# main.net
KiCad netlist of a schematic drawn in EAGLE
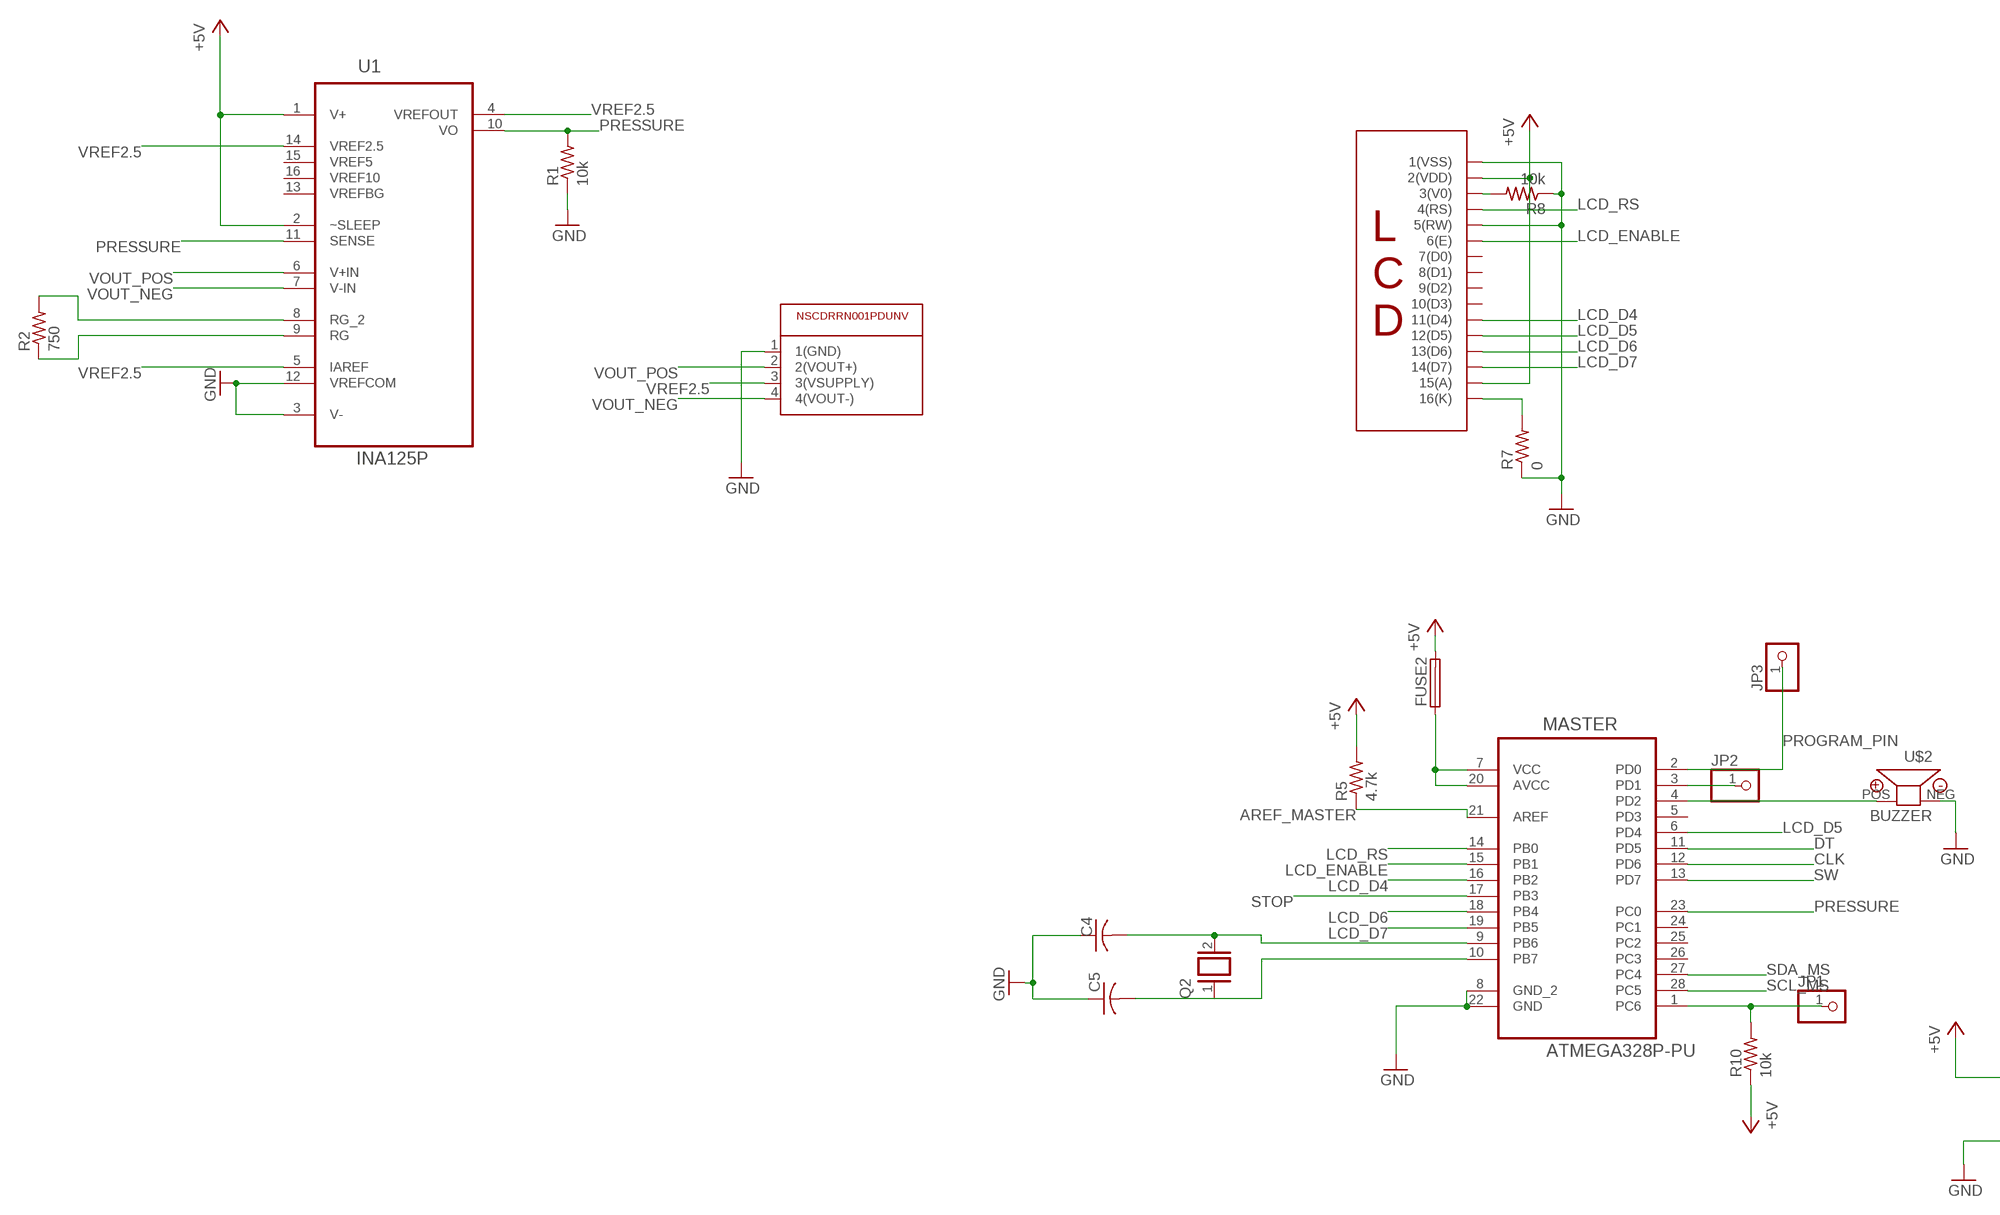
[diagram p0: schematic, sheet 1, part 1 of 2]
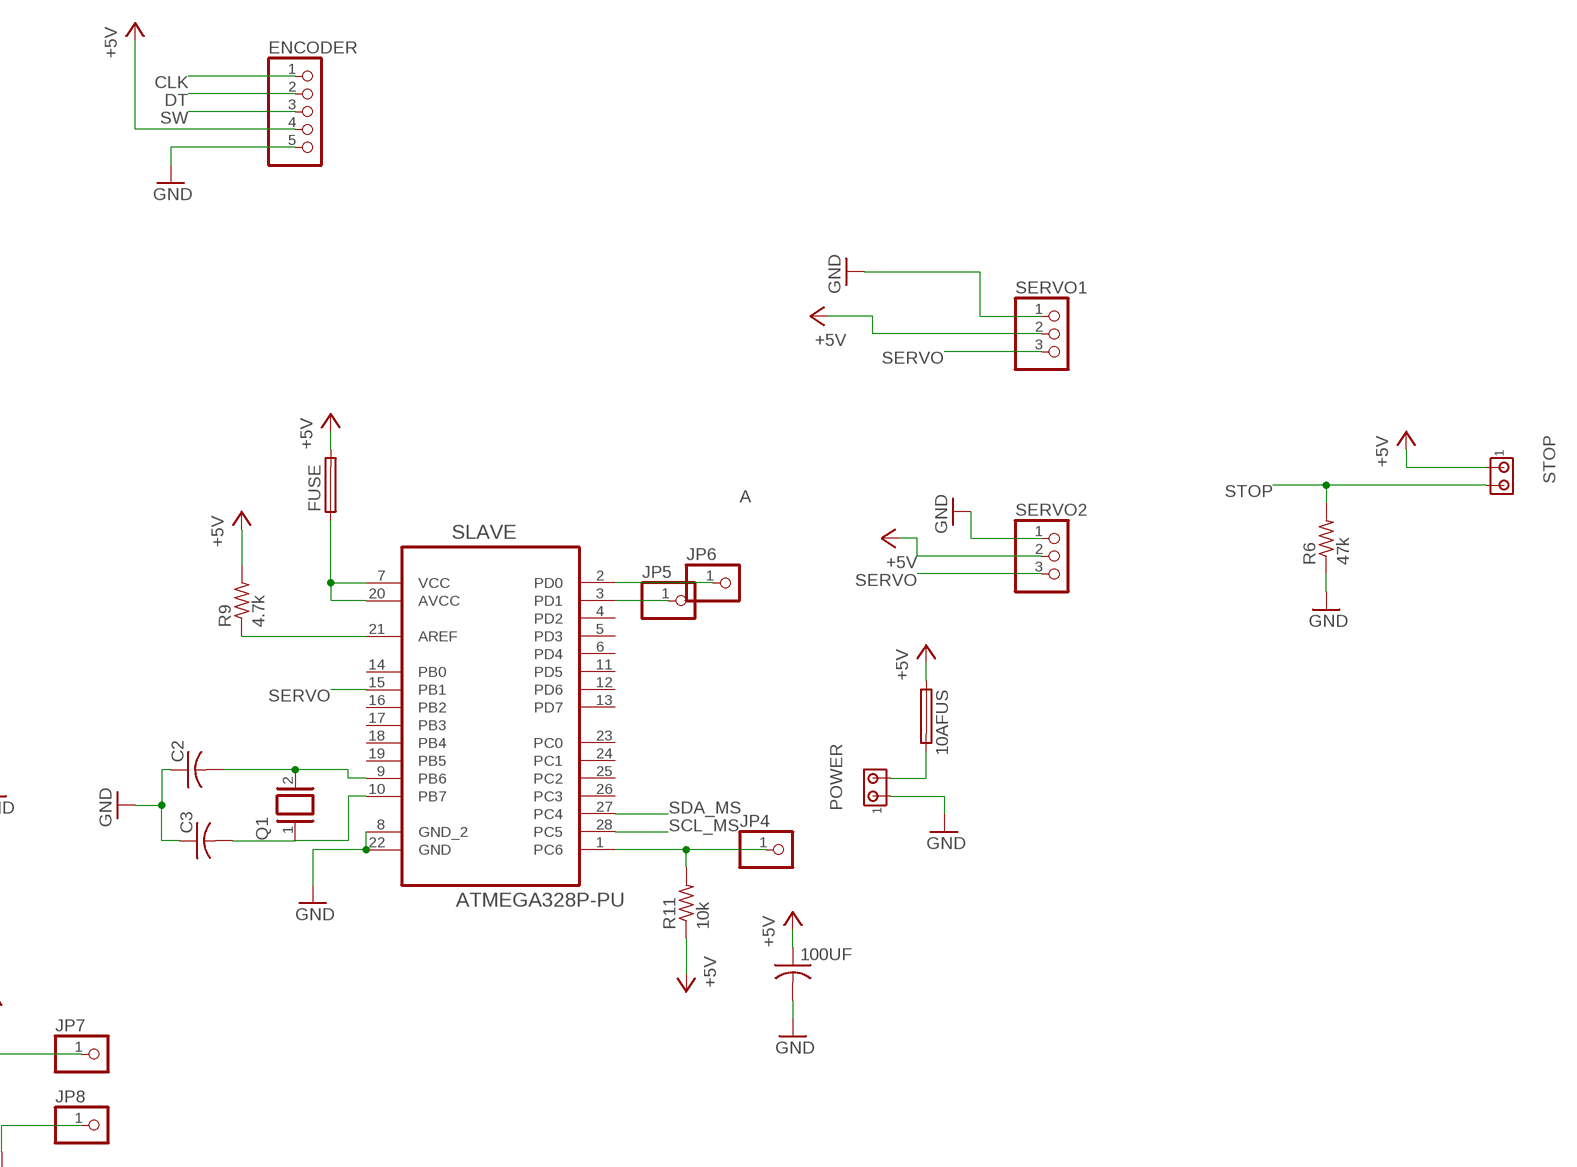
[diagram p1: schematic, sheet 1, part 2 of 2]

(export (version "E")
  (design (tool "Eeschema 10.0.6"))
  (components
    (comp (ref "10AFUS")
      (value "FUSE050-075X075")
      (footprint "eagle-import:C050-075X075")
      (libsource (lib "eagle-import") (part "FUSE050-075X075"))
    )
    (comp (ref "100UF")
      (value "5MM_CAPACITOR050-075X075")
      (footprint "eagle-import:C050-075X075")
      (libsource (lib "eagle-import") (part "5MM_CAPACITOR050-075X075"))
    )
    (comp (ref "C2")
      (value "5MM_CAPACITOR050-075X075")
      (footprint "eagle-import:C050-075X075")
      (libsource (lib "eagle-import") (part "5MM_CAPACITOR050-075X075"))
    )
    (comp (ref "C3")
      (value "5MM_CAPACITOR050-075X075")
      (footprint "eagle-import:C050-075X075")
      (libsource (lib "eagle-import") (part "5MM_CAPACITOR050-075X075"))
    )
    (comp (ref "C4")
      (value "5MM_CAPACITOR050-075X075")
      (footprint "eagle-import:C050-075X075")
      (libsource (lib "eagle-import") (part "5MM_CAPACITOR050-075X075"))
    )
    (comp (ref "C5")
      (value "5MM_CAPACITOR050-075X075")
      (footprint "eagle-import:C050-075X075")
      (libsource (lib "eagle-import") (part "5MM_CAPACITOR050-075X075"))
    )
    (comp (ref "ENCODER")
      (value "PINHD-1X5")
      (footprint "eagle-import:1X05")
      (libsource (lib "eagle-import") (part "PINHD-1X5"))
    )
    (comp (ref "FUSE")
      (value "FUSE050-075X075")
      (footprint "eagle-import:C050-075X075")
      (libsource (lib "eagle-import") (part "FUSE050-075X075"))
    )
    (comp (ref "FUSE2")
      (value "FUSE050-075X075")
      (footprint "eagle-import:C050-075X075")
      (libsource (lib "eagle-import") (part "FUSE050-075X075"))
    )
    (comp (ref "JP1")
      (value "PINHD-1X1")
      (footprint "eagle-import:1X01")
      (libsource (lib "eagle-import") (part "PINHD-1X1"))
    )
    (comp (ref "JP2")
      (value "PINHD-1X1")
      (footprint "eagle-import:1X01")
      (libsource (lib "eagle-import") (part "PINHD-1X1"))
    )
    (comp (ref "JP3")
      (value "PINHD-1X1")
      (footprint "eagle-import:1X01")
      (libsource (lib "eagle-import") (part "PINHD-1X1"))
    )
    (comp (ref "JP4")
      (value "PINHD-1X1")
      (footprint "eagle-import:1X01")
      (libsource (lib "eagle-import") (part "PINHD-1X1"))
    )
    (comp (ref "JP5")
      (value "PINHD-1X1")
      (footprint "eagle-import:1X01")
      (libsource (lib "eagle-import") (part "PINHD-1X1"))
    )
    (comp (ref "JP6")
      (value "PINHD-1X1")
      (footprint "eagle-import:1X01")
      (libsource (lib "eagle-import") (part "PINHD-1X1"))
    )
    (comp (ref "JP7")
      (value "PINHD-1X1")
      (footprint "eagle-import:1X01")
      (libsource (lib "eagle-import") (part "PINHD-1X1"))
    )
    (comp (ref "JP8")
      (value "PINHD-1X1")
      (footprint "eagle-import:1X01")
      (libsource (lib "eagle-import") (part "PINHD-1X1"))
    )
    (comp (ref "MASTER")
      (value "ATMEGA328P-PU")
      (footprint "eagle-import:DIP254P762X457-28")
      (fields (field (name "MF") "Microchip"))
      (libsource (lib "eagle-import") (part "ATMEGA328P-PU"))
    )
    (comp (ref "POWER")
      (value "MTA02-156")
      (footprint "eagle-import:1X2MTA")
      (libsource (lib "eagle-import") (part "MTA02-156"))
    )
    (comp (ref "Q1")
      (value "XTAL/S")
      (footprint "eagle-import:QS")
      (libsource (lib "eagle-import") (part "XTAL/S"))
    )
    (comp (ref "Q2")
      (value "XTAL/S")
      (footprint "eagle-import:QS")
      (libsource (lib "eagle-import") (part "XTAL/S"))
    )
    (comp (ref "R1")
      (value "10k")
      (footprint "eagle-import:0207_10")
      (libsource (lib "eagle-import") (part "R-US_0207/10"))
    )
    (comp (ref "R2")
      (value "750")
      (footprint "eagle-import:0207_10")
      (libsource (lib "eagle-import") (part "R-US_0207/10"))
    )
    (comp (ref "R5")
      (value "4.7k")
      (footprint "eagle-import:0207_10")
      (libsource (lib "eagle-import") (part "R-US_0207/10"))
    )
    (comp (ref "R6")
      (value "47k")
      (footprint "eagle-import:0207_10")
      (libsource (lib "eagle-import") (part "R-US_0207/10"))
    )
    (comp (ref "R7")
      (value "0")
      (footprint "eagle-import:0207_10")
      (libsource (lib "eagle-import") (part "R-US_0207/10"))
    )
    (comp (ref "R8")
      (value "10k")
      (footprint "eagle-import:0207_10")
      (libsource (lib "eagle-import") (part "R-US_0207/10"))
    )
    (comp (ref "R9")
      (value "4.7k")
      (footprint "eagle-import:0207_10")
      (libsource (lib "eagle-import") (part "R-US_0207/10"))
    )
    (comp (ref "R10")
      (value "10k")
      (footprint "eagle-import:0207_10")
      (libsource (lib "eagle-import") (part "R-US_0207/10"))
    )
    (comp (ref "R11")
      (value "10k")
      (footprint "eagle-import:0207_10")
      (libsource (lib "eagle-import") (part "R-US_0207/10"))
    )
    (comp (ref "SERVO1")
      (value "PINHD-1X3/90")
      (footprint "eagle-import:1X03_90")
      (libsource (lib "eagle-import") (part "PINHD-1X3/90"))
    )
    (comp (ref "SERVO2")
      (value "PINHD-1X3/90")
      (footprint "eagle-import:1X03_90")
      (libsource (lib "eagle-import") (part "PINHD-1X3/90"))
    )
    (comp (ref "SLAVE")
      (value "ATMEGA328P-PU")
      (footprint "eagle-import:DIP254P762X457-28")
      (fields (field (name "MF") "Microchip"))
      (libsource (lib "eagle-import") (part "ATMEGA328P-PU"))
    )
    (comp (ref "STOP")
      (value "MTA02-156")
      (footprint "eagle-import:1X2MTA")
      (libsource (lib "eagle-import") (part "MTA02-156"))
    )
    (comp (ref "U$1")
      (value "LCD")
      (footprint "eagle-import:1X16")
      (libsource (lib "eagle-import") (part "LCD"))
    )
    (comp (ref "U$2")
      (value "BUZZER")
      (footprint "eagle-import:BUZZER")
      (libsource (lib "eagle-import") (part "BUZZER"))
    )
    (comp (ref "U$3")
      (value "PRESSURE_SENSOR")
      (footprint "eagle-import:DIP8-WIDE")
      (libsource (lib "eagle-import") (part "PRESSURE_SENSOR"))
    )
    (comp (ref "U1")
      (value "INA125P")
      (footprint "eagle-import:DIP254P762X508-16")
      (fields (field (name "MF") "Texas Instruments"))
      (libsource (lib "eagle-import") (part "INA125P"))
    )
  )
  (nets
    (net (code "1") (name "+5V") (class "Default")
      (node (ref "100UF") (pin "1") (pinfunction "1_1") (pintype "passive"))
      (node (ref "10AFUS") (pin "1") (pinfunction "1_1") (pintype "passive"))
      (node (ref "ENCODER") (pin "4") (pinfunction "4_4") (pintype "passive"))
      (node (ref "FUSE") (pin "2") (pinfunction "2_2") (pintype "passive"))
      (node (ref "FUSE2") (pin "2") (pinfunction "2_2") (pintype "passive"))
      (node (ref "JP7") (pin "1") (pinfunction "1_1") (pintype "passive"))
      (node (ref "R10") (pin "1") (pinfunction "1_1") (pintype "passive"))
      (node (ref "R11") (pin "1") (pinfunction "1_1") (pintype "passive"))
      (node (ref "R5") (pin "2") (pinfunction "2_2") (pintype "passive"))
      (node (ref "R9") (pin "2") (pinfunction "2_2") (pintype "passive"))
      (node (ref "SERVO1") (pin "2") (pinfunction "2_2") (pintype "passive"))
      (node (ref "SERVO2") (pin "2") (pinfunction "2_2") (pintype "passive"))
      (node (ref "STOP") (pin "1") (pinfunction "1_1") (pintype "passive"))
      (node (ref "U$1") (pin "15") (pinfunction "15(A)_15") (pintype "bidirectional"))
      (node (ref "U$1") (pin "2") (pinfunction "2(VDD)_2") (pintype "bidirectional"))
      (node (ref "U1") (pin "1") (pinfunction "V+_1") (pintype "power_in"))
      (node (ref "U1") (pin "2") (pinfunction "~{SLEEP}_2") (pintype "passive"))
    )
    (net (code "2") (name "/A") (class "Default")
      (node (ref "JP6") (pin "1") (pinfunction "1_1") (pintype "passive"))
      (node (ref "SLAVE") (pin "2") (pinfunction "PD0_2") (pintype "bidirectional"))
    )
    (net (code "3") (name "/AREF_MASTER") (class "Default")
      (node (ref "MASTER") (pin "21") (pinfunction "AREF_21") (pintype "input"))
      (node (ref "R5") (pin "1") (pinfunction "1_1") (pintype "passive"))
    )
    (net (code "4") (name "/CLK") (class "Default")
      (node (ref "ENCODER") (pin "1") (pinfunction "1_1") (pintype "passive"))
      (node (ref "MASTER") (pin "12") (pinfunction "PD6_12") (pintype "bidirectional"))
    )
    (net (code "5") (name "/DT") (class "Default")
      (node (ref "ENCODER") (pin "2") (pinfunction "2_2") (pintype "passive"))
      (node (ref "MASTER") (pin "11") (pinfunction "PD5_11") (pintype "bidirectional"))
    )
    (net (code "6") (name "/LCD_D4") (class "Default")
      (node (ref "MASTER") (pin "16") (pinfunction "PB2_16") (pintype "bidirectional"))
      (node (ref "U$1") (pin "11") (pinfunction "11(D4)_11") (pintype "bidirectional"))
    )
    (net (code "7") (name "/LCD_D5") (class "Default")
      (node (ref "MASTER") (pin "6") (pinfunction "PD4_6") (pintype "bidirectional"))
      (node (ref "U$1") (pin "12") (pinfunction "12(D5)_12") (pintype "bidirectional"))
    )
    (net (code "8") (name "/LCD_D6") (class "Default")
      (node (ref "MASTER") (pin "18") (pinfunction "PB4_18") (pintype "bidirectional"))
      (node (ref "U$1") (pin "13") (pinfunction "13(D6)_13") (pintype "bidirectional"))
    )
    (net (code "9") (name "/LCD_D7") (class "Default")
      (node (ref "MASTER") (pin "19") (pinfunction "PB5_19") (pintype "bidirectional"))
      (node (ref "U$1") (pin "14") (pinfunction "14(D7)_14") (pintype "bidirectional"))
    )
    (net (code "10") (name "/LCD_ENABLE") (class "Default")
      (node (ref "MASTER") (pin "15") (pinfunction "PB1_15") (pintype "bidirectional"))
      (node (ref "U$1") (pin "6") (pinfunction "6(E)_6") (pintype "bidirectional"))
    )
    (net (code "11") (name "/LCD_RS") (class "Default")
      (node (ref "MASTER") (pin "14") (pinfunction "PB0_14") (pintype "bidirectional"))
      (node (ref "U$1") (pin "4") (pinfunction "4(RS)_4") (pintype "bidirectional"))
    )
    (net (code "12") (name "/PRESSURE") (class "Default")
      (node (ref "MASTER") (pin "23") (pinfunction "PC0_23") (pintype "bidirectional"))
      (node (ref "R1") (pin "2") (pinfunction "2_2") (pintype "passive"))
      (node (ref "U1") (pin "10") (pinfunction "VO_10") (pintype "output"))
      (node (ref "U1") (pin "11") (pinfunction "SENSE_11") (pintype "input"))
    )
    (net (code "13") (name "/PROGRAM_PIN") (class "Default")
      (node (ref "JP3") (pin "1") (pinfunction "1_1") (pintype "passive"))
      (node (ref "MASTER") (pin "2") (pinfunction "PD0_2") (pintype "bidirectional"))
    )
    (net (code "14") (name "/SCL_MS") (class "Default")
      (node (ref "MASTER") (pin "28") (pinfunction "PC5_28") (pintype "bidirectional"))
      (node (ref "SLAVE") (pin "28") (pinfunction "PC5_28") (pintype "bidirectional"))
    )
    (net (code "15") (name "/SDA_MS") (class "Default")
      (node (ref "MASTER") (pin "27") (pinfunction "PC4_27") (pintype "bidirectional"))
      (node (ref "SLAVE") (pin "27") (pinfunction "PC4_27") (pintype "bidirectional"))
    )
    (net (code "16") (name "/SERVO") (class "Default")
      (node (ref "SERVO1") (pin "3") (pinfunction "3_3") (pintype "passive"))
      (node (ref "SERVO2") (pin "3") (pinfunction "3_3") (pintype "passive"))
      (node (ref "SLAVE") (pin "15") (pinfunction "PB1_15") (pintype "bidirectional"))
    )
    (net (code "17") (name "/STOP") (class "Default")
      (node (ref "MASTER") (pin "17") (pinfunction "PB3_17") (pintype "bidirectional"))
      (node (ref "R6") (pin "2") (pinfunction "2_2") (pintype "passive"))
      (node (ref "STOP") (pin "2") (pinfunction "2_2") (pintype "passive"))
    )
    (net (code "18") (name "/SW") (class "Default")
      (node (ref "ENCODER") (pin "3") (pinfunction "3_3") (pintype "passive"))
      (node (ref "MASTER") (pin "13") (pinfunction "PD7_13") (pintype "bidirectional"))
    )
    (net (code "19") (name "/VOUT_NEG") (class "Default")
      (node (ref "U$3") (pin "4") (pinfunction "4(VOUT-)_4") (pintype "bidirectional"))
      (node (ref "U1") (pin "7") (pinfunction "V-IN_7") (pintype "power_in"))
    )
    (net (code "20") (name "/VOUT_POS") (class "Default")
      (node (ref "U$3") (pin "2") (pinfunction "2(VOUT+)_2") (pintype "bidirectional"))
      (node (ref "U1") (pin "6") (pinfunction "V+IN_6") (pintype "power_in"))
    )
    (net (code "21") (name "/VREF2.5") (class "Default")
      (node (ref "U$3") (pin "3") (pinfunction "3(VSUPPLY)_3") (pintype "bidirectional"))
      (node (ref "U1") (pin "14") (pinfunction "VREF2.5_14") (pintype "power_in"))
      (node (ref "U1") (pin "4") (pinfunction "VREFOUT_4") (pintype "output"))
      (node (ref "U1") (pin "5") (pinfunction "IAREF_5") (pintype "passive"))
    )
    (net (code "22") (name "/VREF5") (class "Default")
      (node (ref "U1") (pin "15") (pinfunction "VREF5_15") (pintype "power_in"))
    )
    (net (code "23") (name "/VREF10") (class "Default")
      (node (ref "U1") (pin "16") (pinfunction "VREF10_16") (pintype "power_in"))
    )
    (net (code "24") (name "/VREFBG") (class "Default")
      (node (ref "U1") (pin "13") (pinfunction "VREFBG_13") (pintype "power_in"))
    )
    (net (code "25") (name "GND") (class "Default")
      (node (ref "100UF") (pin "2") (pinfunction "2_2") (pintype "passive"))
      (node (ref "C2") (pin "1") (pinfunction "1_1") (pintype "passive"))
      (node (ref "C3") (pin "1") (pinfunction "1_1") (pintype "passive"))
      (node (ref "C4") (pin "1") (pinfunction "1_1") (pintype "passive"))
      (node (ref "C5") (pin "1") (pinfunction "1_1") (pintype "passive"))
      (node (ref "ENCODER") (pin "5") (pinfunction "5_5") (pintype "passive"))
      (node (ref "JP8") (pin "1") (pinfunction "1_1") (pintype "passive"))
      (node (ref "MASTER") (pin "22") (pinfunction "GND_22") (pintype "passive"))
      (node (ref "MASTER") (pin "8") (pinfunction "GND_2_8") (pintype "passive"))
      (node (ref "POWER") (pin "1") (pinfunction "1_1") (pintype "passive"))
      (node (ref "R1") (pin "1") (pinfunction "1_1") (pintype "passive"))
      (node (ref "R6") (pin "1") (pinfunction "1_1") (pintype "passive"))
      (node (ref "R7") (pin "1") (pinfunction "1_1") (pintype "passive"))
      (node (ref "R8") (pin "1") (pinfunction "1_1") (pintype "passive"))
      (node (ref "SERVO1") (pin "1") (pinfunction "1_1") (pintype "passive"))
      (node (ref "SERVO2") (pin "1") (pinfunction "1_1") (pintype "passive"))
      (node (ref "SLAVE") (pin "22") (pinfunction "GND_22") (pintype "passive"))
      (node (ref "SLAVE") (pin "8") (pinfunction "GND_2_8") (pintype "passive"))
      (node (ref "U$1") (pin "1") (pinfunction "1(VSS)_1") (pintype "bidirectional"))
      (node (ref "U$1") (pin "5") (pinfunction "5(RW)_5") (pintype "bidirectional"))
      (node (ref "U$2") (pin "NEG") (pinfunction "NEG_NEG") (pintype "passive"))
      (node (ref "U$3") (pin "1") (pinfunction "1(GND)_1") (pintype "bidirectional"))
      (node (ref "U1") (pin "12") (pinfunction "VREFCOM_12") (pintype "passive"))
      (node (ref "U1") (pin "3") (pinfunction "V-_3") (pintype "power_in"))
    )
    (net (code "26") (name "Net-(10AFUS-Pad2)") (class "Default")
      (node (ref "10AFUS") (pin "2") (pinfunction "2_2") (pintype "passive"))
      (node (ref "POWER") (pin "2") (pinfunction "2_2") (pintype "passive"))
    )
    (net (code "27") (name "Net-(MASTER-AVCC)") (class "Default")
      (node (ref "FUSE2") (pin "1") (pinfunction "1_1") (pintype "passive"))
      (node (ref "MASTER") (pin "20") (pinfunction "AVCC_20") (pintype "power_in"))
      (node (ref "MASTER") (pin "7") (pinfunction "VCC_7") (pintype "power_in"))
    )
    (net (code "28") (name "Net-(MASTER-PB6)") (class "Default")
      (node (ref "C4") (pin "2") (pinfunction "2_2") (pintype "passive"))
      (node (ref "MASTER") (pin "9") (pinfunction "PB6_9") (pintype "bidirectional"))
      (node (ref "Q2") (pin "2") (pinfunction "2_2") (pintype "passive"))
    )
    (net (code "29") (name "Net-(MASTER-PB7)") (class "Default")
      (node (ref "C5") (pin "2") (pinfunction "2_2") (pintype "passive"))
      (node (ref "MASTER") (pin "10") (pinfunction "PB7_10") (pintype "bidirectional"))
      (node (ref "Q2") (pin "1") (pinfunction "1_1") (pintype "passive"))
    )
    (net (code "30") (name "Net-(MASTER-PC6)") (class "Default")
      (node (ref "JP1") (pin "1") (pinfunction "1_1") (pintype "passive"))
      (node (ref "MASTER") (pin "1") (pinfunction "PC6_1") (pintype "bidirectional"))
      (node (ref "R10") (pin "2") (pinfunction "2_2") (pintype "passive"))
    )
    (net (code "31") (name "Net-(MASTER-PD1)") (class "Default")
      (node (ref "JP2") (pin "1") (pinfunction "1_1") (pintype "passive"))
      (node (ref "MASTER") (pin "3") (pinfunction "PD1_3") (pintype "bidirectional"))
    )
    (net (code "32") (name "Net-(MASTER-PD2)") (class "Default")
      (node (ref "MASTER") (pin "4") (pinfunction "PD2_4") (pintype "bidirectional"))
      (node (ref "U$2") (pin "POS") (pinfunction "POS_POS") (pintype "passive"))
    )
    (net (code "33") (name "Net-(SLAVE-AREF)") (class "Default")
      (node (ref "R9") (pin "1") (pinfunction "1_1") (pintype "passive"))
      (node (ref "SLAVE") (pin "21") (pinfunction "AREF_21") (pintype "input"))
    )
    (net (code "34") (name "Net-(SLAVE-AVCC)") (class "Default")
      (node (ref "FUSE") (pin "1") (pinfunction "1_1") (pintype "passive"))
      (node (ref "SLAVE") (pin "20") (pinfunction "AVCC_20") (pintype "power_in"))
      (node (ref "SLAVE") (pin "7") (pinfunction "VCC_7") (pintype "power_in"))
    )
    (net (code "35") (name "Net-(SLAVE-PB6)") (class "Default")
      (node (ref "C2") (pin "2") (pinfunction "2_2") (pintype "passive"))
      (node (ref "Q1") (pin "2") (pinfunction "2_2") (pintype "passive"))
      (node (ref "SLAVE") (pin "9") (pinfunction "PB6_9") (pintype "bidirectional"))
    )
    (net (code "36") (name "Net-(SLAVE-PB7)") (class "Default")
      (node (ref "C3") (pin "2") (pinfunction "2_2") (pintype "passive"))
      (node (ref "Q1") (pin "1") (pinfunction "1_1") (pintype "passive"))
      (node (ref "SLAVE") (pin "10") (pinfunction "PB7_10") (pintype "bidirectional"))
    )
    (net (code "37") (name "Net-(SLAVE-PC6)") (class "Default")
      (node (ref "JP4") (pin "1") (pinfunction "1_1") (pintype "passive"))
      (node (ref "R11") (pin "2") (pinfunction "2_2") (pintype "passive"))
      (node (ref "SLAVE") (pin "1") (pinfunction "PC6_1") (pintype "bidirectional"))
    )
    (net (code "38") (name "Net-(SLAVE-PD1)") (class "Default")
      (node (ref "JP5") (pin "1") (pinfunction "1_1") (pintype "passive"))
      (node (ref "SLAVE") (pin "3") (pinfunction "PD1_3") (pintype "bidirectional"))
    )
    (net (code "39") (name "Net-(U$1-3(V0))") (class "Default")
      (node (ref "R8") (pin "2") (pinfunction "2_2") (pintype "passive"))
      (node (ref "U$1") (pin "3") (pinfunction "3(V0)_3") (pintype "bidirectional"))
    )
    (net (code "40") (name "Net-(U$1-16(K))") (class "Default")
      (node (ref "R7") (pin "2") (pinfunction "2_2") (pintype "passive"))
      (node (ref "U$1") (pin "16") (pinfunction "16(K)_16") (pintype "bidirectional"))
    )
    (net (code "41") (name "Net-(U1-RG)") (class "Default")
      (node (ref "R2") (pin "1") (pinfunction "1_1") (pintype "passive"))
      (node (ref "U1") (pin "9") (pinfunction "RG_9") (pintype "passive"))
    )
    (net (code "42") (name "Net-(U1-RG_2)") (class "Default")
      (node (ref "R2") (pin "2") (pinfunction "2_2") (pintype "passive"))
      (node (ref "U1") (pin "8") (pinfunction "RG_2_8") (pintype "passive"))
    )
    (net (code "43") (name "unconnected-(MASTER-PC1-Pad24)") (class "Default")
      (node (ref "MASTER") (pin "24") (pinfunction "PC1_24") (pintype "bidirectional"))
    )
    (net (code "44") (name "unconnected-(MASTER-PC2-Pad25)") (class "Default")
      (node (ref "MASTER") (pin "25") (pinfunction "PC2_25") (pintype "bidirectional"))
    )
    (net (code "45") (name "unconnected-(MASTER-PC3-Pad26)") (class "Default")
      (node (ref "MASTER") (pin "26") (pinfunction "PC3_26") (pintype "bidirectional"))
    )
    (net (code "46") (name "unconnected-(MASTER-PD3-Pad5)") (class "Default")
      (node (ref "MASTER") (pin "5") (pinfunction "PD3_5") (pintype "bidirectional"))
    )
    (net (code "47") (name "unconnected-(SLAVE-PB0-Pad14)") (class "Default")
      (node (ref "SLAVE") (pin "14") (pinfunction "PB0_14") (pintype "bidirectional"))
    )
    (net (code "48") (name "unconnected-(SLAVE-PB2-Pad16)") (class "Default")
      (node (ref "SLAVE") (pin "16") (pinfunction "PB2_16") (pintype "bidirectional"))
    )
    (net (code "49") (name "unconnected-(SLAVE-PB3-Pad17)") (class "Default")
      (node (ref "SLAVE") (pin "17") (pinfunction "PB3_17") (pintype "bidirectional"))
    )
    (net (code "50") (name "unconnected-(SLAVE-PB4-Pad18)") (class "Default")
      (node (ref "SLAVE") (pin "18") (pinfunction "PB4_18") (pintype "bidirectional"))
    )
    (net (code "51") (name "unconnected-(SLAVE-PB5-Pad19)") (class "Default")
      (node (ref "SLAVE") (pin "19") (pinfunction "PB5_19") (pintype "bidirectional"))
    )
    (net (code "52") (name "unconnected-(SLAVE-PC0-Pad23)") (class "Default")
      (node (ref "SLAVE") (pin "23") (pinfunction "PC0_23") (pintype "bidirectional"))
    )
    (net (code "53") (name "unconnected-(SLAVE-PC1-Pad24)") (class "Default")
      (node (ref "SLAVE") (pin "24") (pinfunction "PC1_24") (pintype "bidirectional"))
    )
    (net (code "54") (name "unconnected-(SLAVE-PC2-Pad25)") (class "Default")
      (node (ref "SLAVE") (pin "25") (pinfunction "PC2_25") (pintype "bidirectional"))
    )
    (net (code "55") (name "unconnected-(SLAVE-PC3-Pad26)") (class "Default")
      (node (ref "SLAVE") (pin "26") (pinfunction "PC3_26") (pintype "bidirectional"))
    )
    (net (code "56") (name "unconnected-(SLAVE-PD2-Pad4)") (class "Default")
      (node (ref "SLAVE") (pin "4") (pinfunction "PD2_4") (pintype "bidirectional"))
    )
    (net (code "57") (name "unconnected-(SLAVE-PD3-Pad5)") (class "Default")
      (node (ref "SLAVE") (pin "5") (pinfunction "PD3_5") (pintype "bidirectional"))
    )
    (net (code "58") (name "unconnected-(SLAVE-PD4-Pad6)") (class "Default")
      (node (ref "SLAVE") (pin "6") (pinfunction "PD4_6") (pintype "bidirectional"))
    )
    (net (code "59") (name "unconnected-(SLAVE-PD5-Pad11)") (class "Default")
      (node (ref "SLAVE") (pin "11") (pinfunction "PD5_11") (pintype "bidirectional"))
    )
    (net (code "60") (name "unconnected-(SLAVE-PD6-Pad12)") (class "Default")
      (node (ref "SLAVE") (pin "12") (pinfunction "PD6_12") (pintype "bidirectional"))
    )
    (net (code "61") (name "unconnected-(SLAVE-PD7-Pad13)") (class "Default")
      (node (ref "SLAVE") (pin "13") (pinfunction "PD7_13") (pintype "bidirectional"))
    )
    (net (code "62") (name "unconnected-(U$1-7(D0)-Pad7)") (class "Default")
      (node (ref "U$1") (pin "7") (pinfunction "7(D0)_7") (pintype "bidirectional"))
    )
    (net (code "63") (name "unconnected-(U$1-8(D1)-Pad8)") (class "Default")
      (node (ref "U$1") (pin "8") (pinfunction "8(D1)_8") (pintype "bidirectional"))
    )
    (net (code "64") (name "unconnected-(U$1-9(D2)-Pad9)") (class "Default")
      (node (ref "U$1") (pin "9") (pinfunction "9(D2)_9") (pintype "bidirectional"))
    )
    (net (code "65") (name "unconnected-(U$1-10(D3)-Pad10)") (class "Default")
      (node (ref "U$1") (pin "10") (pinfunction "10(D3)_10") (pintype "bidirectional"))
    )
  )
)
